# SPI_CAN_Converter.net
KiCad netlist of a schematic drawn in EAGLE
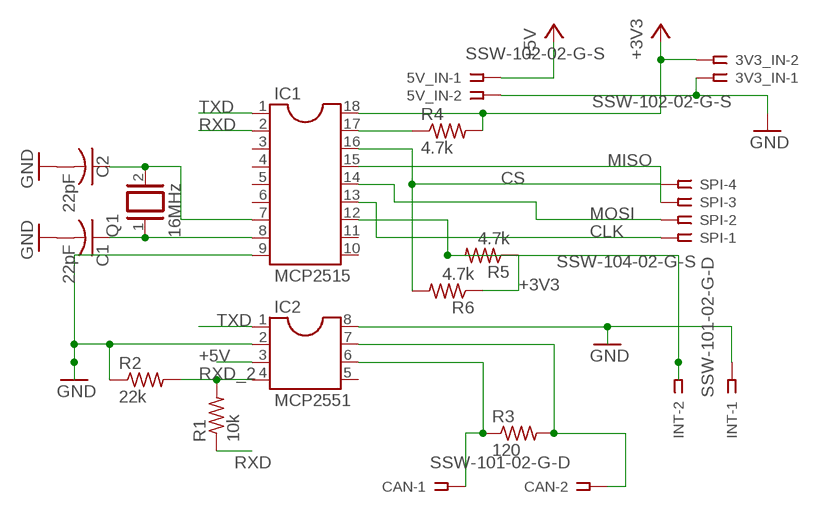
[diagram p0: schematic, sheet 1]

(export (version "E")
  (design (tool "Eeschema 10.0.6"))
  (components
    (comp (ref "3V3_IN")
      (value "SSW-102-02-G-S")
      (footprint "eagle-import:SSW-102-02-G-S")
      (fields (field (name "MF") "Samtec Inc."))
      (libsource (lib "eagle-import") (part "SSW-102-02-G-S"))
    )
    (comp (ref "5V_IN")
      (value "SSW-102-02-G-S")
      (footprint "eagle-import:SSW-102-02-G-S")
      (fields (field (name "MF") "Samtec Inc."))
      (libsource (lib "eagle-import") (part "SSW-102-02-G-S"))
    )
    (comp (ref "C1")
      (value "22pF")
      (footprint "eagle-import:C050-024X044")
      (libsource (lib "eagle-import") (part "C-US050-024X044"))
    )
    (comp (ref "C2")
      (value "22pF")
      (footprint "eagle-import:C050-024X044")
      (libsource (lib "eagle-import") (part "C-US050-024X044"))
    )
    (comp (ref "CAN")
      (value "SSW-101-02-G-D")
      (footprint "eagle-import:SSW-101-02-G-D")
      (fields (field (name "MF") "Samtec Inc."))
      (libsource (lib "eagle-import") (part "SSW-101-02-G-D"))
    )
    (comp (ref "IC1")
      (value "MCP2515")
      (footprint "eagle-import:DIL18")
      (libsource (lib "eagle-import") (part "DIL18"))
    )
    (comp (ref "IC2")
      (value "MCP2551")
      (footprint "eagle-import:DIL08")
      (libsource (lib "eagle-import") (part "DIL8"))
    )
    (comp (ref "INT")
      (value "SSW-101-02-G-D")
      (footprint "eagle-import:SSW-101-02-G-D")
      (fields (field (name "MF") "Samtec Inc."))
      (libsource (lib "eagle-import") (part "SSW-101-02-G-D"))
    )
    (comp (ref "Q1")
      (value "16MHz")
      (footprint "eagle-import:QS")
      (libsource (lib "eagle-import") (part "XTAL/S"))
    )
    (comp (ref "R1")
      (value "10k")
      (footprint "eagle-import:0207_7")
      (libsource (lib "eagle-import") (part "R-US_0207/7"))
    )
    (comp (ref "R2")
      (value "22k")
      (footprint "eagle-import:0207_7")
      (libsource (lib "eagle-import") (part "R-US_0207/7"))
    )
    (comp (ref "R3")
      (value "120")
      (footprint "eagle-import:0207_7")
      (libsource (lib "eagle-import") (part "R-US_0207/7"))
    )
    (comp (ref "R4")
      (value "4.7k")
      (footprint "eagle-import:0207_7")
      (libsource (lib "eagle-import") (part "R-US_0207/7"))
    )
    (comp (ref "R5")
      (value "4.7k")
      (footprint "eagle-import:0207_7")
      (libsource (lib "eagle-import") (part "R-US_0207/7"))
    )
    (comp (ref "R6")
      (value "4.7k")
      (footprint "eagle-import:0207_7")
      (libsource (lib "eagle-import") (part "R-US_0207/7"))
    )
    (comp (ref "SPI")
      (value "SSW-104-02-G-S")
      (footprint "eagle-import:SSW-104-02-G-S")
      (fields (field (name "MF") "Samtec Inc."))
      (libsource (lib "eagle-import") (part "SSW-104-02-G-S"))
    )
  )
  (nets
    (net (code "1") (name "+3V3") (class "Default")
      (node (ref "3V3_IN") (pin "2") (pinfunction "1_2") (pintype "passive"))
      (node (ref "IC1") (pin "18") (pinfunction "18_18") (pintype "passive"))
      (node (ref "R4") (pin "2") (pinfunction "2_2") (pintype "passive"))
      (node (ref "R5") (pin "1") (pinfunction "1_1") (pintype "passive"))
      (node (ref "R6") (pin "1") (pinfunction "1_1") (pintype "passive"))
    )
    (net (code "2") (name "+5V") (class "Default")
      (node (ref "5V_IN") (pin "1") (pinfunction "1_1") (pintype "passive"))
      (node (ref "IC2") (pin "3") (pinfunction "3_3") (pintype "passive"))
    )
    (net (code "3") (name "/CLK") (class "Default")
      (node (ref "IC1") (pin "13") (pinfunction "13_13") (pintype "passive"))
      (node (ref "SPI") (pin "1") (pinfunction "1_1") (pintype "passive"))
    )
    (net (code "4") (name "/CS") (class "Default")
      (node (ref "IC1") (pin "16") (pinfunction "16_16") (pintype "passive"))
      (node (ref "R6") (pin "2") (pinfunction "2_2") (pintype "passive"))
      (node (ref "SPI") (pin "4") (pinfunction "1_4") (pintype "passive"))
    )
    (net (code "5") (name "/MISO") (class "Default")
      (node (ref "IC1") (pin "15") (pinfunction "15_15") (pintype "passive"))
      (node (ref "SPI") (pin "3") (pinfunction "1_3") (pintype "passive"))
    )
    (net (code "6") (name "/MOSI") (class "Default")
      (node (ref "IC1") (pin "14") (pinfunction "14_14") (pintype "passive"))
      (node (ref "SPI") (pin "2") (pinfunction "1_2") (pintype "passive"))
    )
    (net (code "7") (name "/RXD") (class "Default")
      (node (ref "IC1") (pin "2") (pinfunction "2_2") (pintype "passive"))
      (node (ref "R1") (pin "1") (pinfunction "1_1") (pintype "passive"))
    )
    (net (code "8") (name "/RXD_2") (class "Default")
      (node (ref "IC2") (pin "4") (pinfunction "4_4") (pintype "passive"))
      (node (ref "R1") (pin "2") (pinfunction "2_2") (pintype "passive"))
      (node (ref "R2") (pin "2") (pinfunction "2_2") (pintype "passive"))
    )
    (net (code "9") (name "/TXD") (class "Default")
      (node (ref "IC1") (pin "1") (pinfunction "1_1") (pintype "passive"))
      (node (ref "IC2") (pin "1") (pinfunction "1_1") (pintype "passive"))
    )
    (net (code "10") (name "GND") (class "Default")
      (node (ref "3V3_IN") (pin "1") (pinfunction "1_1") (pintype "passive"))
      (node (ref "5V_IN") (pin "2") (pinfunction "1_2") (pintype "passive"))
      (node (ref "C1") (pin "2") (pinfunction "2_2") (pintype "passive"))
      (node (ref "C2") (pin "2") (pinfunction "2_2") (pintype "passive"))
      (node (ref "IC1") (pin "9") (pinfunction "9_9") (pintype "passive"))
      (node (ref "IC2") (pin "2") (pinfunction "2_2") (pintype "passive"))
      (node (ref "IC2") (pin "8") (pinfunction "8_8") (pintype "passive"))
      (node (ref "INT") (pin "1") (pinfunction "1_1") (pintype "passive"))
      (node (ref "R2") (pin "1") (pinfunction "1_1") (pintype "passive"))
    )
    (net (code "11") (name "Net-(C1-Pad1)") (class "Default")
      (node (ref "C1") (pin "1") (pinfunction "1_1") (pintype "passive"))
      (node (ref "IC1") (pin "8") (pinfunction "8_8") (pintype "passive"))
      (node (ref "Q1") (pin "1") (pinfunction "1_1") (pintype "passive"))
    )
    (net (code "12") (name "Net-(C2-Pad1)") (class "Default")
      (node (ref "C2") (pin "1") (pinfunction "1_1") (pintype "passive"))
      (node (ref "IC1") (pin "7") (pinfunction "7_7") (pintype "passive"))
      (node (ref "Q1") (pin "2") (pinfunction "2_2") (pintype "passive"))
    )
    (net (code "13") (name "Net-(CAN-Pad1)") (class "Default")
      (node (ref "CAN") (pin "1") (pinfunction "1_1") (pintype "passive"))
      (node (ref "IC2") (pin "6") (pinfunction "6_6") (pintype "passive"))
      (node (ref "R3") (pin "1") (pinfunction "1_1") (pintype "passive"))
    )
    (net (code "14") (name "Net-(CANB-1)") (class "Default")
      (node (ref "CAN") (pin "2") (pinfunction "1_2") (pintype "passive"))
      (node (ref "IC2") (pin "7") (pinfunction "7_7") (pintype "passive"))
      (node (ref "R3") (pin "2") (pinfunction "2_2") (pintype "passive"))
    )
    (net (code "15") (name "Net-(IC1-Pad17)") (class "Default")
      (node (ref "IC1") (pin "17") (pinfunction "17_17") (pintype "passive"))
      (node (ref "R4") (pin "1") (pinfunction "1_1") (pintype "passive"))
    )
    (net (code "16") (name "Net-(INTB-1)") (class "Default")
      (node (ref "IC1") (pin "12") (pinfunction "12_12") (pintype "passive"))
      (node (ref "INT") (pin "2") (pinfunction "1_2") (pintype "passive"))
      (node (ref "R5") (pin "2") (pinfunction "2_2") (pintype "passive"))
    )
    (net (code "17") (name "unconnected-(IC1-Pad3)") (class "Default")
      (node (ref "IC1") (pin "3") (pinfunction "3_3") (pintype "passive"))
    )
    (net (code "18") (name "unconnected-(IC1-Pad4)") (class "Default")
      (node (ref "IC1") (pin "4") (pinfunction "4_4") (pintype "passive"))
    )
    (net (code "19") (name "unconnected-(IC1-Pad5)") (class "Default")
      (node (ref "IC1") (pin "5") (pinfunction "5_5") (pintype "passive"))
    )
    (net (code "20") (name "unconnected-(IC1-Pad6)") (class "Default")
      (node (ref "IC1") (pin "6") (pinfunction "6_6") (pintype "passive"))
    )
    (net (code "21") (name "unconnected-(IC1-Pad10)") (class "Default")
      (node (ref "IC1") (pin "10") (pinfunction "10_10") (pintype "passive"))
    )
    (net (code "22") (name "unconnected-(IC1-Pad11)") (class "Default")
      (node (ref "IC1") (pin "11") (pinfunction "11_11") (pintype "passive"))
    )
    (net (code "23") (name "unconnected-(IC2-Pad5)") (class "Default")
      (node (ref "IC2") (pin "5") (pinfunction "5_5") (pintype "passive"))
    )
  )
)
